# STM32F103_2.net
KiCad netlist of a schematic drawn in Altium Designer
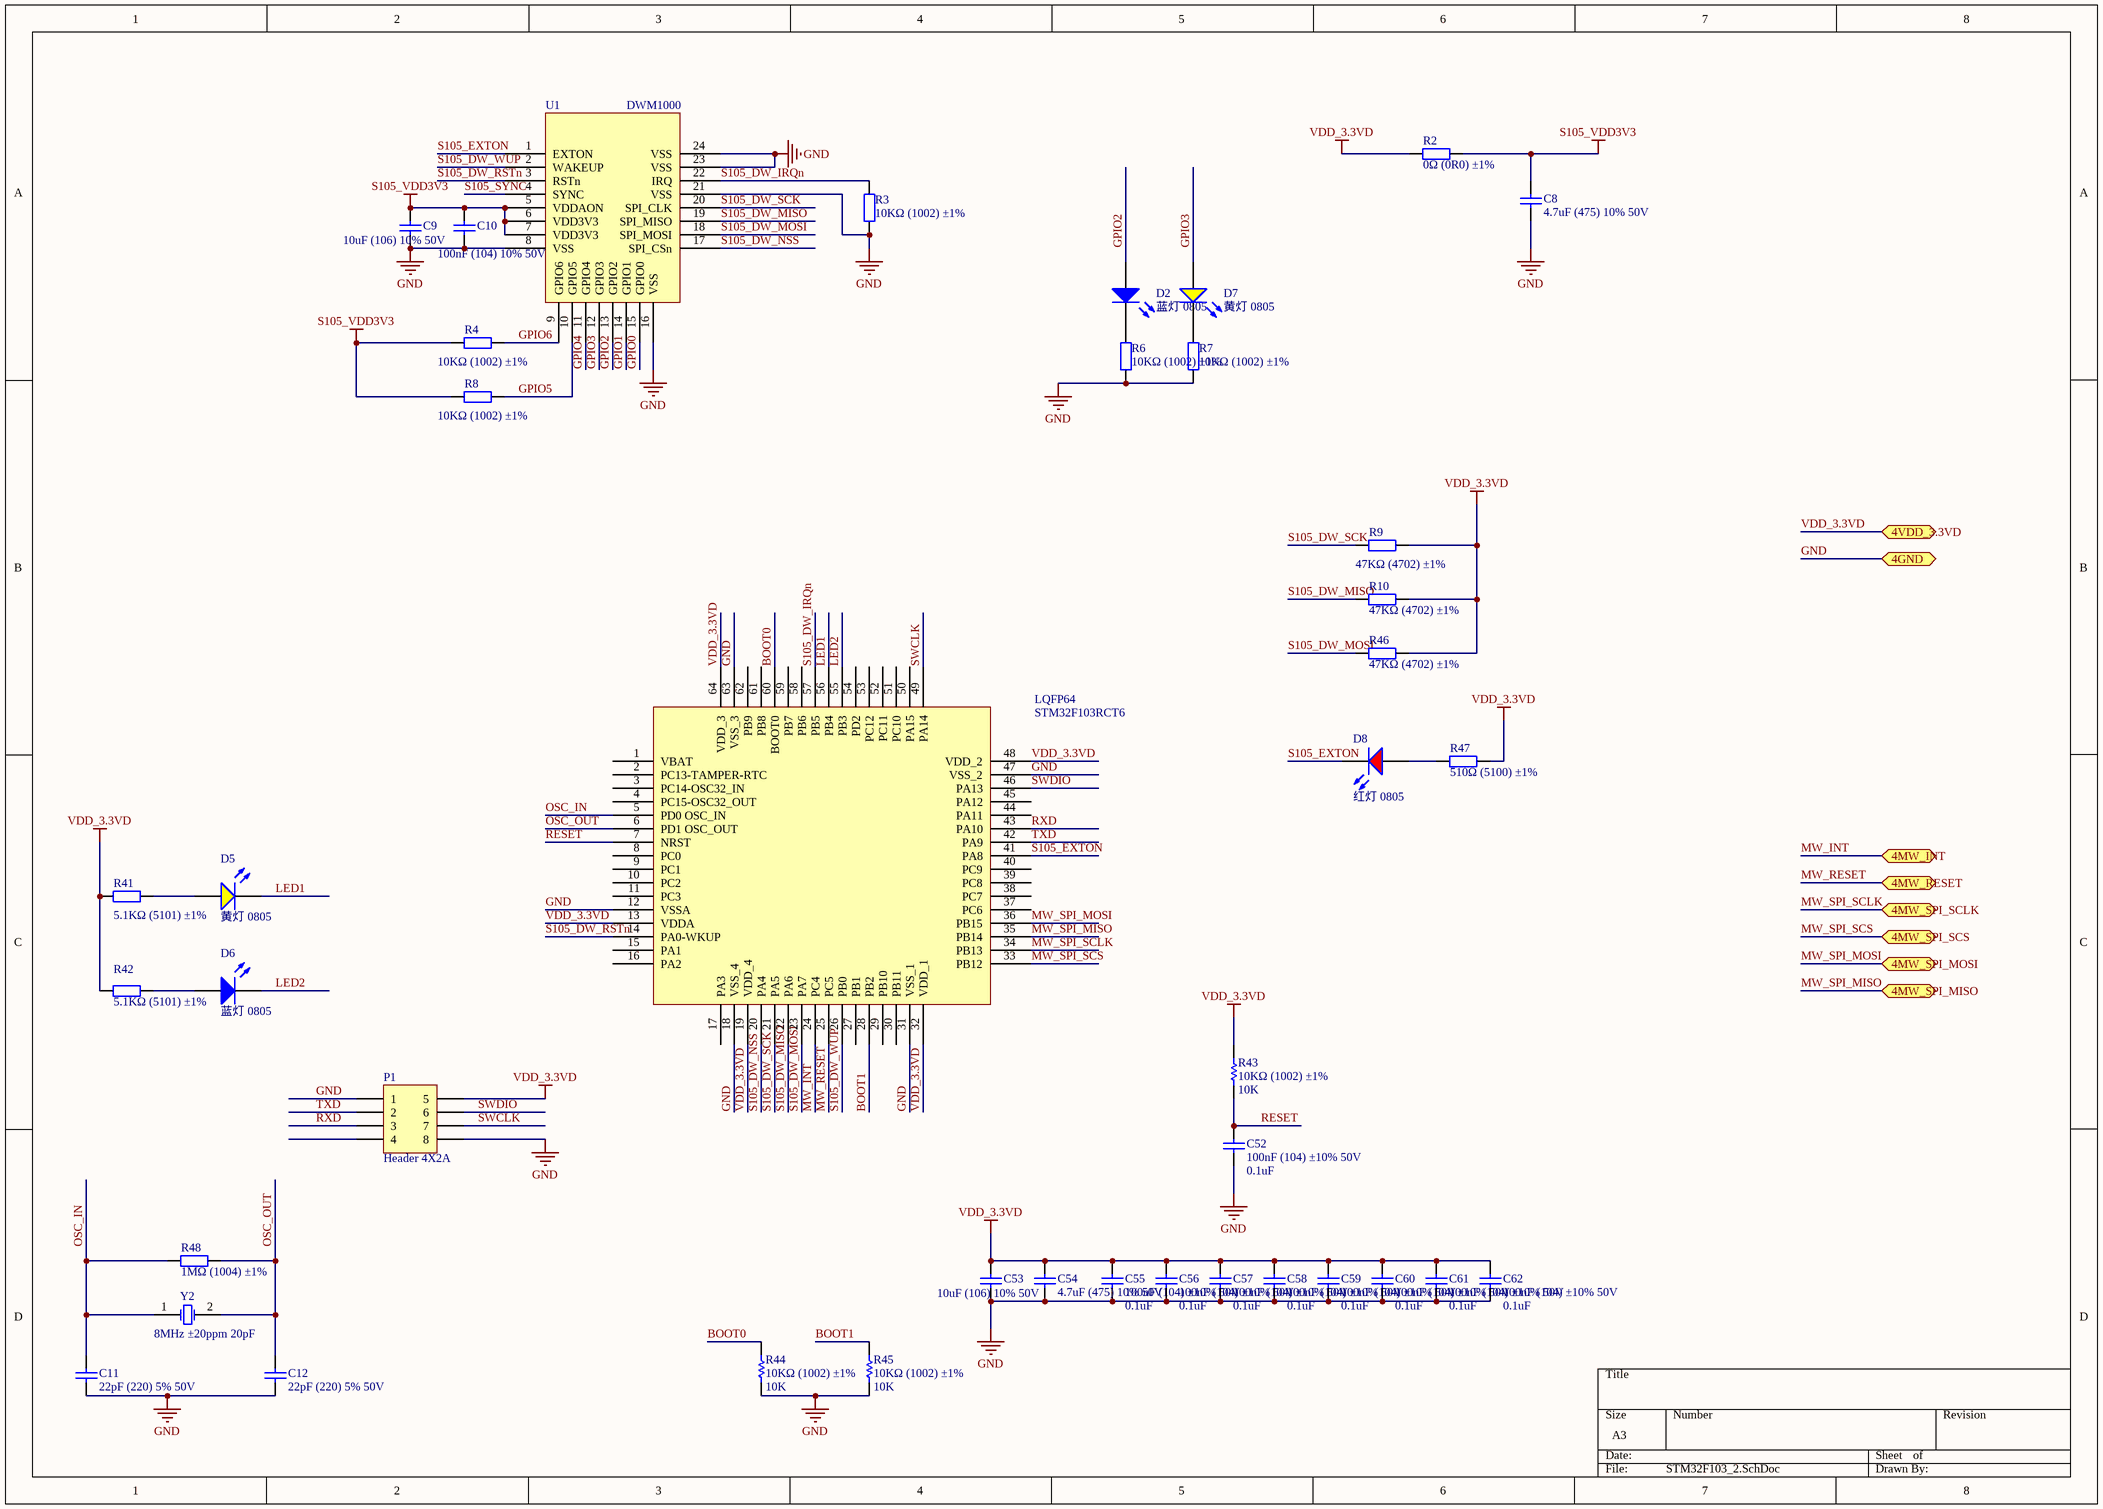
[diagram p0: STM32F103_2.SchDoc]

(export (version "E")
  (design (tool "Eeschema 10.0.6"))
  (components
    (comp (ref "C8")
      (value "4.7uF (475) 10% 50V")
      (footprint "1206_C")
      (description "贴片电容")
      (libsource (lib "Miscellaneous Devices LC") (part "1206 4.7uF (475) 10% 50V"))
    )
    (comp (ref "C9")
      (value "10uF (106) 10% 50V")
      (footprint "1206_C")
      (description "贴片电容")
      (libsource (lib "Miscellaneous Devices LC") (part "1206 10uF (106) 10% 50V"))
    )
    (comp (ref "C10")
      (value "100nF (104) 10% 50V")
      (footprint "0603_C")
      (description "贴片电容")
      (libsource (lib "Miscellaneous Devices LC") (part "0603 100nF (104) 10% 50V"))
    )
    (comp (ref "C11")
      (value "22pF (220) 5% 50V")
      (footprint "0603_C")
      (description "贴片电容")
      (libsource (lib "Miscellaneous Devices LC") (part "0603 22pF (220) 5% 50V"))
    )
    (comp (ref "C12")
      (value "22pF (220) 5% 50V")
      (footprint "0603_C")
      (description "贴片电容")
      (libsource (lib "Miscellaneous Devices LC") (part "0603 22pF (220) 5% 50V"))
    )
    (comp (ref "C52")
      (value "100nF (104) ±10% 50V")
      (footprint "1608[0603]")
      (description "Capacitor")
      (fields (field (name "ALTIUM_VALUE") "0.1uF") (field (name "PUBLISHER") "Altium Limited"))
      (libsource (lib "Miscellaneous Devices") (part "Cap"))
    )
    (comp (ref "C53")
      (value "10uF (106) 10% 50V")
      (footprint "1206_C")
      (description "贴片电容")
      (libsource (lib "Miscellaneous Devices LC") (part "1206 10uF (106) 10% 50V"))
    )
    (comp (ref "C54")
      (value "4.7uF (475) 10% 50V")
      (footprint "1206_C")
      (description "贴片电容")
      (libsource (lib "Miscellaneous Devices LC") (part "1206 4.7uF (475) 10% 50V"))
    )
    (comp (ref "C55")
      (value "100nF (104) ±10% 50V")
      (footprint "1608[0603]")
      (description "Capacitor")
      (fields (field (name "ALTIUM_VALUE") "0.1uF") (field (name "PUBLISHER") "Altium Limited"))
      (libsource (lib "Miscellaneous Devices") (part "Cap"))
    )
    (comp (ref "C56")
      (value "100nF (104) ±10% 50V")
      (footprint "1608[0603]")
      (description "Capacitor")
      (fields (field (name "ALTIUM_VALUE") "0.1uF") (field (name "PUBLISHER") "Altium Limited"))
      (libsource (lib "Miscellaneous Devices") (part "Cap"))
    )
    (comp (ref "C57")
      (value "100nF (104) ±10% 50V")
      (footprint "1608[0603]")
      (description "Capacitor")
      (fields (field (name "ALTIUM_VALUE") "0.1uF") (field (name "PUBLISHER") "Altium Limited"))
      (libsource (lib "Miscellaneous Devices") (part "Cap"))
    )
    (comp (ref "C58")
      (value "100nF (104) ±10% 50V")
      (footprint "1608[0603]")
      (description "Capacitor")
      (fields (field (name "ALTIUM_VALUE") "0.1uF") (field (name "PUBLISHER") "Altium Limited"))
      (libsource (lib "Miscellaneous Devices") (part "Cap"))
    )
    (comp (ref "C59")
      (value "100nF (104) ±10% 50V")
      (footprint "1608[0603]")
      (description "Capacitor")
      (fields (field (name "ALTIUM_VALUE") "0.1uF") (field (name "PUBLISHER") "Altium Limited"))
      (libsource (lib "Miscellaneous Devices") (part "Cap"))
    )
    (comp (ref "C60")
      (value "100nF (104) ±10% 50V")
      (footprint "1608[0603]")
      (description "Capacitor")
      (fields (field (name "ALTIUM_VALUE") "0.1uF") (field (name "PUBLISHER") "Altium Limited"))
      (libsource (lib "Miscellaneous Devices") (part "Cap"))
    )
    (comp (ref "C61")
      (value "100nF (104) ±10% 50V")
      (footprint "1608[0603]")
      (description "Capacitor")
      (fields (field (name "ALTIUM_VALUE") "0.1uF") (field (name "PUBLISHER") "Altium Limited"))
      (libsource (lib "Miscellaneous Devices") (part "Cap"))
    )
    (comp (ref "C62")
      (value "100nF (104) ±10% 50V")
      (footprint "1608[0603]")
      (description "Capacitor")
      (fields (field (name "ALTIUM_VALUE") "0.1uF") (field (name "PUBLISHER") "Altium Limited"))
      (libsource (lib "Miscellaneous Devices") (part "Cap"))
    )
    (comp (ref "D2")
      (value "蓝灯 0805")
      (footprint "0805_LED_S1")
      (description "发光二极管")
      (libsource (lib "Miscellaneous Devices LC") (part "0805 蓝灯"))
    )
    (comp (ref "D5")
      (value "黄灯 0805")
      (footprint "0805_LED_S1")
      (description "发光二极管")
      (libsource (lib "Miscellaneous Devices LC") (part "0805 黄灯"))
    )
    (comp (ref "D6")
      (value "蓝灯 0805")
      (footprint "0805_LED_S1")
      (description "发光二极管")
      (libsource (lib "Miscellaneous Devices LC") (part "0805 蓝灯"))
    )
    (comp (ref "D7")
      (value "黄灯 0805")
      (footprint "0805_LED_S1")
      (description "发光二极管")
      (libsource (lib "Miscellaneous Devices LC") (part "0805 黄灯"))
    )
    (comp (ref "D8")
      (value "红灯 0805")
      (footprint "0805_LED_S1")
      (description "发光二极管")
      (libsource (lib "Miscellaneous Devices LC") (part "0805 红灯"))
    )
    (comp (ref "LQFP64")
      (value "STM32F103RCT6")
      (footprint "LQFP64")
      (libsource (lib "LS_Schlib1") (part "STM32F103RCT6"))
    )
    (comp (ref "P1")
      (value "Header 4X2A")
      (footprint "HDR2X4_CEN")
      (description "Header, 4-Pin, Dual row")
      (fields (field (name "PUBLISHER") "Altium Limited"))
      (libsource (lib "Miscellaneous Connectors") (part "Header 4X2A"))
    )
    (comp (ref "R2")
      (value "0Ω (0R0) ±1%")
      (footprint "1206_R")
      (description "贴片电阻")
      (libsource (lib "Miscellaneous Devices LC") (part "1206 0Ω (0R0) 1%"))
    )
    (comp (ref "R3")
      (value "10KΩ (1002) ±1%")
      (footprint "0603_R")
      (description "贴片电阻")
      (libsource (lib "") (part "0603 10KΩ (1002) 1%_1"))
    )
    (comp (ref "R4")
      (value "10KΩ (1002) ±1%")
      (footprint "0603_R")
      (description "贴片电阻")
      (libsource (lib "Miscellaneous Devices LC") (part "0603 10KΩ (1002) 1%"))
    )
    (comp (ref "R6")
      (value "10KΩ (1002) ±1%")
      (footprint "0603_R")
      (description "贴片电阻")
      (libsource (lib "") (part "0603 10KΩ (1002) 1%_1"))
    )
    (comp (ref "R7")
      (value "10KΩ (1002) ±1%")
      (footprint "0603_R")
      (description "贴片电阻")
      (libsource (lib "") (part "0603 10KΩ (1002) 1%_1"))
    )
    (comp (ref "R8")
      (value "10KΩ (1002) ±1%")
      (footprint "0603_R")
      (description "贴片电阻")
      (libsource (lib "Miscellaneous Devices LC") (part "0603 10KΩ (1002) 1%"))
    )
    (comp (ref "R9")
      (value "47KΩ (4702) ±1%")
      (footprint "0603_R")
      (description "贴片电阻")
      (libsource (lib "Miscellaneous Devices LC") (part "0603 47KΩ (4702) 1%"))
    )
    (comp (ref "R10")
      (value "47KΩ (4702) ±1%")
      (footprint "0603_R")
      (description "贴片电阻")
      (libsource (lib "Miscellaneous Devices LC") (part "0603 47KΩ (4702) 1%"))
    )
    (comp (ref "R41")
      (value "5.1KΩ (5101) ±1%")
      (footprint "0603_R")
      (description "贴片电阻")
      (libsource (lib "Miscellaneous Devices LC") (part "0603 5.1KΩ (5101) 1%"))
    )
    (comp (ref "R42")
      (value "5.1KΩ (5101) ±1%")
      (footprint "0603_R")
      (description "贴片电阻")
      (libsource (lib "Miscellaneous Devices LC") (part "0603 5.1KΩ (5101) 1%"))
    )
    (comp (ref "R43")
      (value "10KΩ (1002) ±1%")
      (footprint "1608[0603]")
      (description "Resistor")
      (fields (field (name "ALTIUM_VALUE") "10K") (field (name "PUBLISHER") "Altium Limited"))
      (libsource (lib "Miscellaneous Devices") (part "Res1"))
    )
    (comp (ref "R44")
      (value "10KΩ (1002) ±1%")
      (footprint "1608[0603]")
      (description "Resistor")
      (fields (field (name "ALTIUM_VALUE") "10K") (field (name "PUBLISHER") "Altium Limited"))
      (libsource (lib "Miscellaneous Devices") (part "Res1"))
    )
    (comp (ref "R45")
      (value "10KΩ (1002) ±1%")
      (footprint "1608[0603]")
      (description "Resistor")
      (fields (field (name "ALTIUM_VALUE") "10K") (field (name "PUBLISHER") "Altium Limited"))
      (libsource (lib "Miscellaneous Devices") (part "Res1"))
    )
    (comp (ref "R46")
      (value "47KΩ (4702) ±1%")
      (footprint "0603_R")
      (description "贴片电阻")
      (libsource (lib "Miscellaneous Devices LC") (part "0603 47KΩ (4702) 1%"))
    )
    (comp (ref "R47")
      (value "510Ω (5100) ±1%")
      (footprint "0603_R")
      (description "贴片电阻")
      (libsource (lib "Miscellaneous Devices LC") (part "0603 510Ω (5100) 1%"))
    )
    (comp (ref "R48")
      (value "1MΩ (1004) ±1%")
      (footprint "0603_R")
      (description "贴片电阻")
      (libsource (lib "Miscellaneous Devices LC") (part "0603 1MΩ (1004) 1%"))
    )
    (comp (ref "U1")
      (value "DWM1000")
      (footprint "DWM1000")
      (libsource (lib "UWB_Location") (part "DWM1000"))
    )
    (comp (ref "Y2")
      (value "8MHz ±20ppm 20pF")
      (footprint "SMD-5032_2P")
      (description "贴片晶振")
      (libsource (lib "Miscellaneous Devices LC") (part "SMD-5032_2P 8MHz 20ppm 20pF"))
    )
  )
  (nets
    (net (code "1") (name "/BOOT0") (class "Default")
      (node (ref "LQFP64") (pin "60") (pinfunction "BOOT0_60") (pintype "passive"))
      (node (ref "R44") (pin "2") (pinfunction "2_2") (pintype "passive"))
    )
    (net (code "2") (name "/BOOT1") (class "Default")
      (node (ref "LQFP64") (pin "28") (pinfunction "PB2_28") (pintype "passive"))
      (node (ref "R45") (pin "2") (pinfunction "2_2") (pintype "passive"))
    )
    (net (code "3") (name "/GPIO0") (class "Default")
      (node (ref "U1") (pin "15") (pinfunction "GPIO0_15") (pintype "passive"))
    )
    (net (code "4") (name "/GPIO1") (class "Default")
      (node (ref "U1") (pin "14") (pinfunction "GPIO1_14") (pintype "passive"))
    )
    (net (code "5") (name "/GPIO2") (class "Default")
      (node (ref "D2") (pin "A") (pinfunction "A_A") (pintype "passive"))
      (node (ref "U1") (pin "13") (pinfunction "GPIO2_13") (pintype "passive"))
    )
    (net (code "6") (name "/GPIO3") (class "Default")
      (node (ref "D7") (pin "A") (pinfunction "A_A") (pintype "passive"))
      (node (ref "U1") (pin "12") (pinfunction "GPIO3_12") (pintype "passive"))
    )
    (net (code "7") (name "/GPIO4") (class "Default")
      (node (ref "U1") (pin "11") (pinfunction "GPIO4_11") (pintype "passive"))
    )
    (net (code "8") (name "/GPIO5") (class "Default")
      (node (ref "R8") (pin "2") (pinfunction "2_2") (pintype "passive"))
      (node (ref "U1") (pin "10") (pinfunction "GPIO5_10") (pintype "passive"))
    )
    (net (code "9") (name "/GPIO6") (class "Default")
      (node (ref "R4") (pin "2") (pinfunction "2_2") (pintype "passive"))
      (node (ref "U1") (pin "9") (pinfunction "GPIO6_9") (pintype "passive"))
    )
    (net (code "10") (name "/LED1") (class "Default")
      (node (ref "D5") (pin "K") (pinfunction "K_K") (pintype "passive"))
      (node (ref "LQFP64") (pin "56") (pinfunction "PB4_56") (pintype "passive"))
    )
    (net (code "11") (name "/LED2") (class "Default")
      (node (ref "D6") (pin "K") (pinfunction "K_K") (pintype "passive"))
      (node (ref "LQFP64") (pin "55") (pinfunction "PB3_55") (pintype "passive"))
    )
    (net (code "12") (name "/MW_INT") (class "Default")
      (node (ref "LQFP64") (pin "24") (pinfunction "PC4_24") (pintype "passive"))
    )
    (net (code "13") (name "/MW_RESET") (class "Default")
      (node (ref "LQFP64") (pin "25") (pinfunction "PC5_25") (pintype "passive"))
    )
    (net (code "14") (name "/MW_SPI_MISO") (class "Default")
      (node (ref "LQFP64") (pin "35") (pinfunction "PB14_35") (pintype "passive"))
    )
    (net (code "15") (name "/MW_SPI_MOSI") (class "Default")
      (node (ref "LQFP64") (pin "36") (pinfunction "PB15_36") (pintype "passive"))
    )
    (net (code "16") (name "/MW_SPI_SCLK") (class "Default")
      (node (ref "LQFP64") (pin "34") (pinfunction "PB13_34") (pintype "passive"))
    )
    (net (code "17") (name "/MW_SPI_SCS") (class "Default")
      (node (ref "LQFP64") (pin "33") (pinfunction "PB12_33") (pintype "passive"))
    )
    (net (code "18") (name "/OSC_IN") (class "Default")
      (node (ref "C11") (pin "2") (pinfunction "2_2") (pintype "passive"))
      (node (ref "LQFP64") (pin "5") (pinfunction "PD0_OSC_IN_5") (pintype "passive"))
      (node (ref "R48") (pin "1") (pinfunction "1_1") (pintype "passive"))
      (node (ref "Y2") (pin "1") (pinfunction "OSC1_1") (pintype "passive"))
    )
    (net (code "19") (name "/OSC_OUT") (class "Default")
      (node (ref "C12") (pin "2") (pinfunction "2_2") (pintype "passive"))
      (node (ref "LQFP64") (pin "6") (pinfunction "PD1_OSC_OUT_6") (pintype "passive"))
      (node (ref "R48") (pin "2") (pinfunction "2_2") (pintype "passive"))
      (node (ref "Y2") (pin "2") (pinfunction "OSC2_2") (pintype "passive"))
    )
    (net (code "20") (name "/RESET") (class "Default")
      (node (ref "C52") (pin "2") (pinfunction "2_2") (pintype "passive"))
      (node (ref "LQFP64") (pin "7") (pinfunction "NRST_7") (pintype "passive"))
      (node (ref "R43") (pin "1") (pinfunction "1_1") (pintype "passive"))
    )
    (net (code "21") (name "/RXD") (class "Default")
      (node (ref "LQFP64") (pin "43") (pinfunction "PA10_43") (pintype "passive"))
      (node (ref "P1") (pin "3") (pinfunction "3_3") (pintype "passive"))
    )
    (net (code "22") (name "/S105_DW_IRQn") (class "Default")
      (node (ref "LQFP64") (pin "57") (pinfunction "PB5_57") (pintype "passive"))
      (node (ref "R3") (pin "2") (pinfunction "2_2") (pintype "passive"))
      (node (ref "U1") (pin "22") (pinfunction "IRQ_22") (pintype "passive"))
    )
    (net (code "23") (name "/S105_DW_MISO") (class "Default")
      (node (ref "LQFP64") (pin "22") (pinfunction "PA6_22") (pintype "passive"))
      (node (ref "R10") (pin "1") (pinfunction "1_1") (pintype "passive"))
      (node (ref "U1") (pin "19") (pinfunction "SPI_MISO_19") (pintype "passive"))
    )
    (net (code "24") (name "/S105_DW_MOSI") (class "Default")
      (node (ref "LQFP64") (pin "23") (pinfunction "PA7_23") (pintype "passive"))
      (node (ref "R46") (pin "1") (pinfunction "1_1") (pintype "passive"))
      (node (ref "U1") (pin "18") (pinfunction "SPI_MOSI_18") (pintype "passive"))
    )
    (net (code "25") (name "/S105_DW_NSS") (class "Default")
      (node (ref "LQFP64") (pin "20") (pinfunction "PA4_20") (pintype "passive"))
      (node (ref "U1") (pin "17") (pinfunction "SPI_CSn_17") (pintype "passive"))
    )
    (net (code "26") (name "/S105_DW_RSTn") (class "Default")
      (node (ref "LQFP64") (pin "14") (pinfunction "PA0-WKUP_14") (pintype "passive"))
      (node (ref "U1") (pin "3") (pinfunction "RSTn_3") (pintype "passive"))
    )
    (net (code "27") (name "/S105_DW_SCK") (class "Default")
      (node (ref "LQFP64") (pin "21") (pinfunction "PA5_21") (pintype "passive"))
      (node (ref "R9") (pin "1") (pinfunction "1_1") (pintype "passive"))
      (node (ref "U1") (pin "20") (pinfunction "SPI_CLK_20") (pintype "passive"))
    )
    (net (code "28") (name "/S105_DW_WUP") (class "Default")
      (node (ref "LQFP64") (pin "26") (pinfunction "PB0_26") (pintype "passive"))
      (node (ref "U1") (pin "2") (pinfunction "WAKEUP_2") (pintype "passive"))
    )
    (net (code "29") (name "/S105_EXTON") (class "Default")
      (node (ref "D8") (pin "K") (pinfunction "K_K") (pintype "passive"))
      (node (ref "LQFP64") (pin "41") (pinfunction "PA8_41") (pintype "passive"))
      (node (ref "U1") (pin "1") (pinfunction "EXTON_1") (pintype "passive"))
    )
    (net (code "30") (name "/S105_SYNC") (class "Default")
      (node (ref "U1") (pin "4") (pinfunction "SYNC_4") (pintype "passive"))
    )
    (net (code "31") (name "/SWCLK") (class "Default")
      (node (ref "LQFP64") (pin "49") (pinfunction "PA14_49") (pintype "passive"))
      (node (ref "P1") (pin "7") (pinfunction "7_7") (pintype "passive"))
    )
    (net (code "32") (name "/SWDIO") (class "Default")
      (node (ref "LQFP64") (pin "46") (pinfunction "PA13_46") (pintype "passive"))
      (node (ref "P1") (pin "6") (pinfunction "6_6") (pintype "passive"))
    )
    (net (code "33") (name "/TXD") (class "Default")
      (node (ref "LQFP64") (pin "42") (pinfunction "PA9_42") (pintype "passive"))
      (node (ref "P1") (pin "2") (pinfunction "2_2") (pintype "passive"))
    )
    (net (code "34") (name "GND") (class "Default")
      (node (ref "C10") (pin "1") (pinfunction "1_1") (pintype "passive"))
      (node (ref "C11") (pin "1") (pinfunction "1_1") (pintype "passive"))
      (node (ref "C12") (pin "1") (pinfunction "1_1") (pintype "passive"))
      (node (ref "C52") (pin "1") (pinfunction "1_1") (pintype "passive"))
      (node (ref "C53") (pin "1") (pinfunction "1_1") (pintype "passive"))
      (node (ref "C54") (pin "1") (pinfunction "1_1") (pintype "passive"))
      (node (ref "C55") (pin "1") (pinfunction "1_1") (pintype "passive"))
      (node (ref "C56") (pin "1") (pinfunction "1_1") (pintype "passive"))
      (node (ref "C57") (pin "1") (pinfunction "1_1") (pintype "passive"))
      (node (ref "C58") (pin "1") (pinfunction "1_1") (pintype "passive"))
      (node (ref "C59") (pin "1") (pinfunction "1_1") (pintype "passive"))
      (node (ref "C60") (pin "1") (pinfunction "1_1") (pintype "passive"))
      (node (ref "C61") (pin "1") (pinfunction "1_1") (pintype "passive"))
      (node (ref "C62") (pin "1") (pinfunction "1_1") (pintype "passive"))
      (node (ref "C8") (pin "1") (pinfunction "1_1") (pintype "passive"))
      (node (ref "C9") (pin "1") (pinfunction "1_1") (pintype "passive"))
      (node (ref "LQFP64") (pin "12") (pinfunction "VSSA_12") (pintype "passive"))
      (node (ref "LQFP64") (pin "18") (pinfunction "VSS_4_18") (pintype "passive"))
      (node (ref "LQFP64") (pin "31") (pinfunction "VSS_1_31") (pintype "passive"))
      (node (ref "LQFP64") (pin "47") (pinfunction "VSS_2_47") (pintype "passive"))
      (node (ref "LQFP64") (pin "63") (pinfunction "VSS_3_63") (pintype "passive"))
      (node (ref "P1") (pin "1") (pinfunction "1_1") (pintype "passive"))
      (node (ref "P1") (pin "8") (pinfunction "8_8") (pintype "passive"))
      (node (ref "R3") (pin "1") (pinfunction "1_1") (pintype "passive"))
      (node (ref "R44") (pin "1") (pinfunction "1_1") (pintype "passive"))
      (node (ref "R45") (pin "1") (pinfunction "1_1") (pintype "passive"))
      (node (ref "R6") (pin "1") (pinfunction "1_1") (pintype "passive"))
      (node (ref "R7") (pin "1") (pinfunction "1_1") (pintype "passive"))
      (node (ref "U1") (pin "16") (pinfunction "VSS_16") (pintype "passive"))
      (node (ref "U1") (pin "21") (pinfunction "VSS_21") (pintype "passive"))
      (node (ref "U1") (pin "23") (pinfunction "VSS_23") (pintype "passive"))
      (node (ref "U1") (pin "24") (pinfunction "VSS_24") (pintype "passive"))
      (node (ref "U1") (pin "8") (pinfunction "VSS_8") (pintype "passive"))
    )
    (net (code "35") (name "Net-(D2-PadK)") (class "Default")
      (node (ref "D2") (pin "K") (pinfunction "K_K") (pintype "passive"))
      (node (ref "R6") (pin "2") (pinfunction "2_2") (pintype "passive"))
    )
    (net (code "36") (name "Net-(D5-PadA)") (class "Default")
      (node (ref "D5") (pin "A") (pinfunction "A_A") (pintype "passive"))
      (node (ref "R41") (pin "2") (pinfunction "2_2") (pintype "passive"))
    )
    (net (code "37") (name "Net-(D6-PadA)") (class "Default")
      (node (ref "D6") (pin "A") (pinfunction "A_A") (pintype "passive"))
      (node (ref "R42") (pin "2") (pinfunction "2_2") (pintype "passive"))
    )
    (net (code "38") (name "Net-(D7-PadK)") (class "Default")
      (node (ref "D7") (pin "K") (pinfunction "K_K") (pintype "passive"))
      (node (ref "R7") (pin "2") (pinfunction "2_2") (pintype "passive"))
    )
    (net (code "39") (name "Net-(D8-PadA)") (class "Default")
      (node (ref "D8") (pin "A") (pinfunction "A_A") (pintype "passive"))
      (node (ref "R47") (pin "1") (pinfunction "1_1") (pintype "passive"))
    )
    (net (code "40") (name "S105_VDD3V3") (class "Default")
      (node (ref "C10") (pin "2") (pinfunction "2_2") (pintype "passive"))
      (node (ref "C8") (pin "2") (pinfunction "2_2") (pintype "passive"))
      (node (ref "C9") (pin "2") (pinfunction "2_2") (pintype "passive"))
      (node (ref "R2") (pin "2") (pinfunction "2_2") (pintype "passive"))
      (node (ref "R4") (pin "1") (pinfunction "1_1") (pintype "passive"))
      (node (ref "R8") (pin "1") (pinfunction "1_1") (pintype "passive"))
      (node (ref "U1") (pin "5") (pinfunction "VDDAON_5") (pintype "passive"))
      (node (ref "U1") (pin "6") (pinfunction "VDD3V3_6") (pintype "passive"))
      (node (ref "U1") (pin "7") (pinfunction "VDD3V3_7") (pintype "passive"))
    )
    (net (code "41") (name "VDD_3.3VD") (class "Default")
      (node (ref "C53") (pin "2") (pinfunction "2_2") (pintype "passive"))
      (node (ref "C54") (pin "2") (pinfunction "2_2") (pintype "passive"))
      (node (ref "C55") (pin "2") (pinfunction "2_2") (pintype "passive"))
      (node (ref "C56") (pin "2") (pinfunction "2_2") (pintype "passive"))
      (node (ref "C57") (pin "2") (pinfunction "2_2") (pintype "passive"))
      (node (ref "C58") (pin "2") (pinfunction "2_2") (pintype "passive"))
      (node (ref "C59") (pin "2") (pinfunction "2_2") (pintype "passive"))
      (node (ref "C60") (pin "2") (pinfunction "2_2") (pintype "passive"))
      (node (ref "C61") (pin "2") (pinfunction "2_2") (pintype "passive"))
      (node (ref "C62") (pin "2") (pinfunction "2_2") (pintype "passive"))
      (node (ref "LQFP64") (pin "13") (pinfunction "VDDA_13") (pintype "passive"))
      (node (ref "LQFP64") (pin "19") (pinfunction "VDD_4_19") (pintype "passive"))
      (node (ref "LQFP64") (pin "32") (pinfunction "VDD_1_32") (pintype "passive"))
      (node (ref "LQFP64") (pin "48") (pinfunction "VDD_2_48") (pintype "passive"))
      (node (ref "LQFP64") (pin "64") (pinfunction "VDD_3_64") (pintype "passive"))
      (node (ref "P1") (pin "5") (pinfunction "5_5") (pintype "passive"))
      (node (ref "R10") (pin "2") (pinfunction "2_2") (pintype "passive"))
      (node (ref "R2") (pin "1") (pinfunction "1_1") (pintype "passive"))
      (node (ref "R41") (pin "1") (pinfunction "1_1") (pintype "passive"))
      (node (ref "R42") (pin "1") (pinfunction "1_1") (pintype "passive"))
      (node (ref "R43") (pin "2") (pinfunction "2_2") (pintype "passive"))
      (node (ref "R46") (pin "2") (pinfunction "2_2") (pintype "passive"))
      (node (ref "R47") (pin "2") (pinfunction "2_2") (pintype "passive"))
      (node (ref "R9") (pin "2") (pinfunction "2_2") (pintype "passive"))
    )
    (net (code "42") (name "unconnected-(LQFP64-PA1-Pad15)") (class "Default")
      (node (ref "LQFP64") (pin "15") (pinfunction "PA1_15") (pintype "passive"))
    )
    (net (code "43") (name "unconnected-(LQFP64-PA2-Pad16)") (class "Default")
      (node (ref "LQFP64") (pin "16") (pinfunction "PA2_16") (pintype "passive"))
    )
    (net (code "44") (name "unconnected-(LQFP64-PA3-Pad17)") (class "Default")
      (node (ref "LQFP64") (pin "17") (pinfunction "PA3_17") (pintype "passive"))
    )
    (net (code "45") (name "unconnected-(LQFP64-PA11-Pad44)") (class "Default")
      (node (ref "LQFP64") (pin "44") (pinfunction "PA11_44") (pintype "passive"))
    )
    (net (code "46") (name "unconnected-(LQFP64-PA12-Pad45)") (class "Default")
      (node (ref "LQFP64") (pin "45") (pinfunction "PA12_45") (pintype "passive"))
    )
    (net (code "47") (name "unconnected-(LQFP64-PA15-Pad50)") (class "Default")
      (node (ref "LQFP64") (pin "50") (pinfunction "PA15_50") (pintype "passive"))
    )
    (net (code "48") (name "unconnected-(LQFP64-PB1-Pad27)") (class "Default")
      (node (ref "LQFP64") (pin "27") (pinfunction "PB1_27") (pintype "passive"))
    )
    (net (code "49") (name "unconnected-(LQFP64-PB6-Pad58)") (class "Default")
      (node (ref "LQFP64") (pin "58") (pinfunction "PB6_58") (pintype "passive"))
    )
    (net (code "50") (name "unconnected-(LQFP64-PB7-Pad59)") (class "Default")
      (node (ref "LQFP64") (pin "59") (pinfunction "PB7_59") (pintype "passive"))
    )
    (net (code "51") (name "unconnected-(LQFP64-PB8-Pad61)") (class "Default")
      (node (ref "LQFP64") (pin "61") (pinfunction "PB8_61") (pintype "passive"))
    )
    (net (code "52") (name "unconnected-(LQFP64-PB9-Pad62)") (class "Default")
      (node (ref "LQFP64") (pin "62") (pinfunction "PB9_62") (pintype "passive"))
    )
    (net (code "53") (name "unconnected-(LQFP64-PB10-Pad29)") (class "Default")
      (node (ref "LQFP64") (pin "29") (pinfunction "PB10_29") (pintype "passive"))
    )
    (net (code "54") (name "unconnected-(LQFP64-PB11-Pad30)") (class "Default")
      (node (ref "LQFP64") (pin "30") (pinfunction "PB11_30") (pintype "passive"))
    )
    (net (code "55") (name "unconnected-(LQFP64-PC0-Pad8)") (class "Default")
      (node (ref "LQFP64") (pin "8") (pinfunction "PC0_8") (pintype "passive"))
    )
    (net (code "56") (name "unconnected-(LQFP64-PC1-Pad9)") (class "Default")
      (node (ref "LQFP64") (pin "9") (pinfunction "PC1_9") (pintype "passive"))
    )
    (net (code "57") (name "unconnected-(LQFP64-PC2-Pad10)") (class "Default")
      (node (ref "LQFP64") (pin "10") (pinfunction "PC2_10") (pintype "passive"))
    )
    (net (code "58") (name "unconnected-(LQFP64-PC3-Pad11)") (class "Default")
      (node (ref "LQFP64") (pin "11") (pinfunction "PC3_11") (pintype "passive"))
    )
    (net (code "59") (name "unconnected-(LQFP64-PC6-Pad37)") (class "Default")
      (node (ref "LQFP64") (pin "37") (pinfunction "PC6_37") (pintype "passive"))
    )
    (net (code "60") (name "unconnected-(LQFP64-PC7-Pad38)") (class "Default")
      (node (ref "LQFP64") (pin "38") (pinfunction "PC7_38") (pintype "passive"))
    )
    (net (code "61") (name "unconnected-(LQFP64-PC8-Pad39)") (class "Default")
      (node (ref "LQFP64") (pin "39") (pinfunction "PC8_39") (pintype "passive"))
    )
    (net (code "62") (name "unconnected-(LQFP64-PC9-Pad40)") (class "Default")
      (node (ref "LQFP64") (pin "40") (pinfunction "PC9_40") (pintype "passive"))
    )
    (net (code "63") (name "unconnected-(LQFP64-PC10-Pad51)") (class "Default")
      (node (ref "LQFP64") (pin "51") (pinfunction "PC10_51") (pintype "passive"))
    )
    (net (code "64") (name "unconnected-(LQFP64-PC11-Pad52)") (class "Default")
      (node (ref "LQFP64") (pin "52") (pinfunction "PC11_52") (pintype "passive"))
    )
    (net (code "65") (name "unconnected-(LQFP64-PC12-Pad53)") (class "Default")
      (node (ref "LQFP64") (pin "53") (pinfunction "PC12_53") (pintype "passive"))
    )
    (net (code "66") (name "unconnected-(LQFP64-PC13-TAMPER-RTC-Pad2)") (class "Default")
      (node (ref "LQFP64") (pin "2") (pinfunction "PC13-TAMPER-RTC_2") (pintype "passive"))
    )
    (net (code "67") (name "unconnected-(LQFP64-PC14-OSC32_IN-Pad3)") (class "Default")
      (node (ref "LQFP64") (pin "3") (pinfunction "PC14-OSC32_IN_3") (pintype "passive"))
    )
    (net (code "68") (name "unconnected-(LQFP64-PC15-OSC32_OUT-Pad4)") (class "Default")
      (node (ref "LQFP64") (pin "4") (pinfunction "PC15-OSC32_OUT_4") (pintype "passive"))
    )
    (net (code "69") (name "unconnected-(LQFP64-PD2-Pad54)") (class "Default")
      (node (ref "LQFP64") (pin "54") (pinfunction "PD2_54") (pintype "passive"))
    )
    (net (code "70") (name "unconnected-(LQFP64-VBAT-Pad1)") (class "Default")
      (node (ref "LQFP64") (pin "1") (pinfunction "VBAT_1") (pintype "passive"))
    )
    (net (code "71") (name "unconnected-(P1-Pad4)") (class "Default")
      (node (ref "P1") (pin "4") (pinfunction "4_4") (pintype "passive"))
    )
  )
)
